# FRONT_CONN.net
KiCad netlist of a schematic drawn in Altium Designer
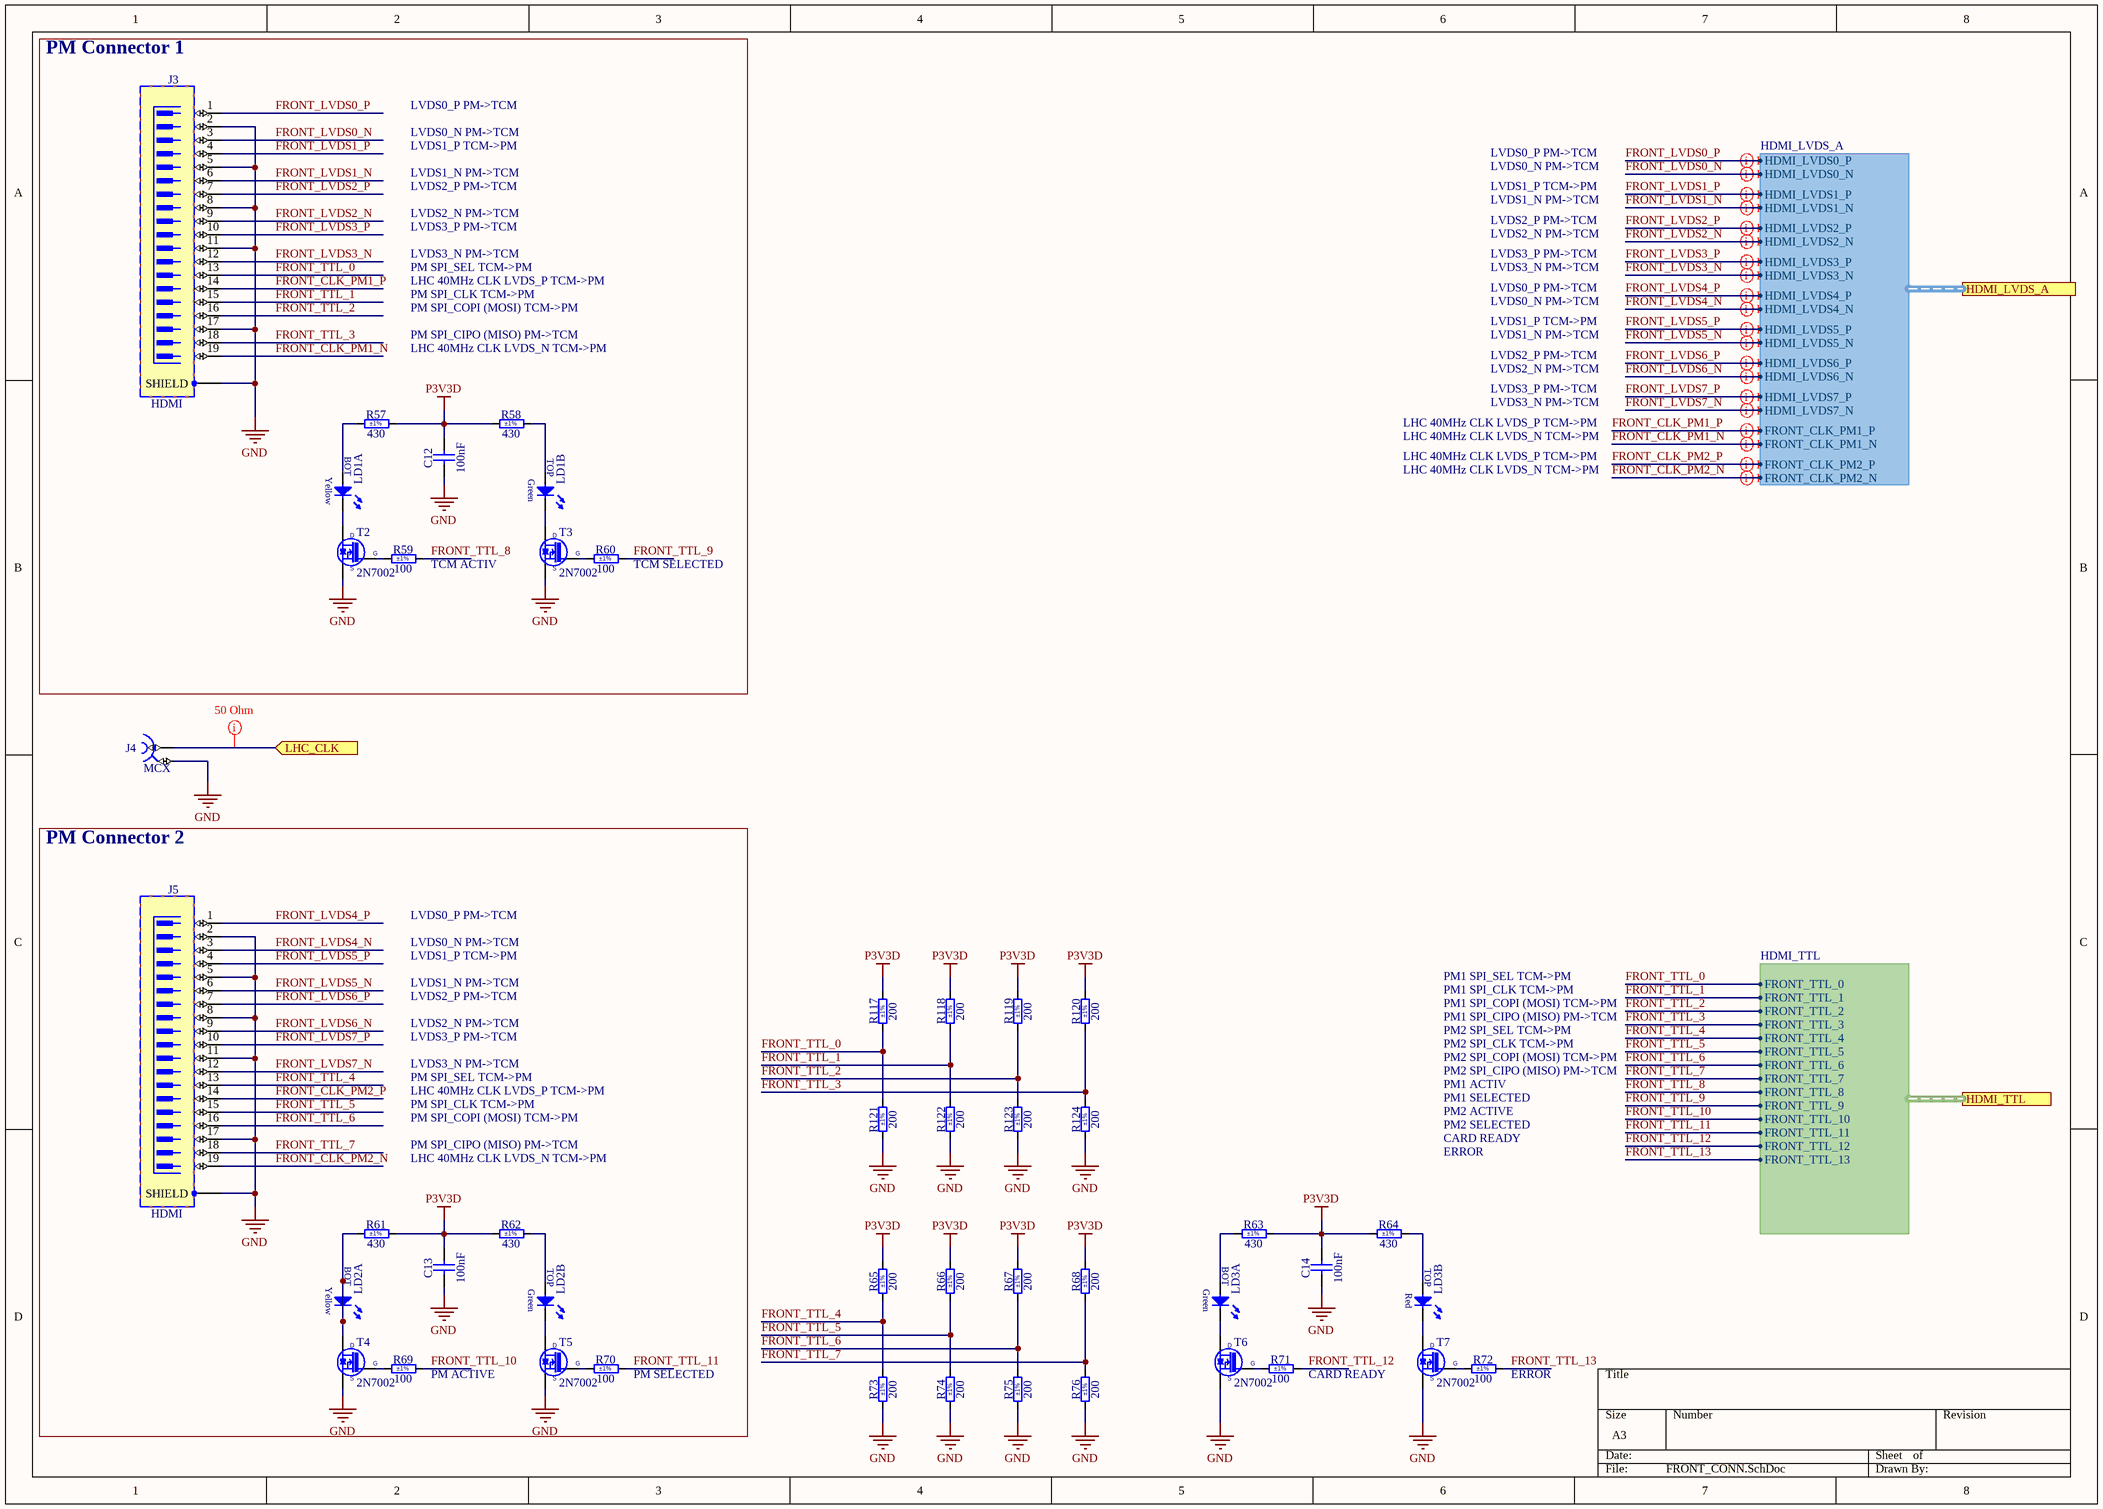
[diagram p0: FRONT_CONN.SchDoc]

(export (version "E")
  (design (tool "Eeschema 10.0.6"))
  (components
    (comp (ref "C12")
      (value "100nF")
      (footprint "CAPC1608X87N")
      (description "Non-polarised capacitor")
      (fields
        (field (name "PART NUMBER") "CC0603_100NF_50V_10%_X7R")
        (field (name "VOLTAGE") "50V")
        (field (name "AUTHOR") "CERN DEM JLC")
      )
      (libsource (lib "Capacitors") (part "Capacitor - non polarized"))
    )
    (comp (ref "C13")
      (value "100nF")
      (footprint "CAPC1608X87N")
      (description "Non-polarised capacitor")
      (fields
        (field (name "PART NUMBER") "CC0603_100NF_50V_10%_X7R")
        (field (name "VOLTAGE") "50V")
        (field (name "AUTHOR") "CERN DEM JLC")
      )
      (libsource (lib "Capacitors") (part "Capacitor - non polarized"))
    )
    (comp (ref "C14")
      (value "100nF")
      (footprint "CAPC1608X87N")
      (description "Non-polarised capacitor")
      (fields
        (field (name "PART NUMBER") "CC0603_100NF_50V_10%_X7R")
        (field (name "VOLTAGE") "50V")
        (field (name "AUTHOR") "CERN DEM JLC")
      )
      (libsource (lib "Capacitors") (part "Capacitor - non polarized"))
    )
    (comp (ref "J3")
      (value "HDMI")
      (footprint "TYCO_2007435-1")
      (description "Connector HDMI 19 Male + 1 Shield")
      (fields
        (field (name "PART NUMBER") "TYCO_2007435-1")
        (field (name "MANUFACTURER") "TYCO ELECTRONICS")
        (field (name "AUTHOR") "CERN DEM MR")
      )
      (libsource (lib "Connectors") (part "Connector HDMI 19 Male + 1 Shield"))
    )
    (comp (ref "J4")
      (value "MCX")
      (footprint "AMPHENOL_919-383J-51A")
      (fields
        (field (name "PART NUMBER") "AMPHENOL_919-383J-51A")
        (field (name "MANUFACTURER") "AMPHENOL")
        (field (name "MANUFACTURER PART NUMBER") "919-383J-51A")
        (field (name "AUTHOR") "CERN DEM BC")
      )
      (libsource (lib "Connectors") (part "Coax_1Female_1Shield"))
    )
    (comp (ref "J5")
      (value "HDMI")
      (footprint "TYCO_2007435-1")
      (description "Connector HDMI 19 Male + 1 Shield")
      (fields
        (field (name "PART NUMBER") "TYCO_2007435-1")
        (field (name "MANUFACTURER") "TYCO ELECTRONICS")
        (field (name "AUTHOR") "CERN DEM MR")
      )
      (libsource (lib "Connectors") (part "Connector HDMI 19 Male + 1 Shield"))
    )
    (comp (ref "LD1")
      (value "Green/Yellow")
      (footprint "LED_DIALIGHT_571-0123F")
      (description "2x LED  Botom Yellow, Top Green")
      (fields
        (field (name "PART NUMBER") "LED_DIALIGHT_571-0123F")
        (field (name "MANUFACTURER") "DIALIGHT")
        (field (name "AUTHOR") "CERN DEM JLC")
      )
      (libsource (lib "ICs And Semiconductors") (part "LED x2 Y-1C2A-BOT_G-3C4A-TOP"))
    )
    (comp (ref "LD2")
      (value "Green/Yellow")
      (footprint "LED_DIALIGHT_571-0123F")
      (description "2x LED  Botom Yellow, Top Green")
      (fields
        (field (name "PART NUMBER") "LED_DIALIGHT_571-0123F")
        (field (name "MANUFACTURER") "DIALIGHT")
        (field (name "AUTHOR") "CERN DEM JLC")
      )
      (libsource (lib "ICs And Semiconductors") (part "LED x2 Y-1C2A-BOT_G-3C4A-TOP"))
    )
    (comp (ref "LD3")
      (value "Red/Green")
      (footprint "LED_DIALIGHT_571-0112-100F")
      (description "2x LED Botom Green, Top Red")
      (fields
        (field (name "PART NUMBER") "LED_DIALIGHT_571-0112-100F")
        (field (name "MANUFACTURER") "DIALIGHT")
        (field (name "AUTHOR") "CERN DEM JLC")
      )
      (libsource (lib "ICs And Semiconductors") (part "LED x2 G-1C2A-BOT_R-3C4A-TOP"))
    )
    (comp (ref "R57")
      (value "430")
      (footprint "RESC1608X55N")
      (description "Resistor - 1%")
      (fields
        (field (name "TOLERANCE") "±1%")
        (field (name "PART NUMBER") "R0603_430R_1%_0.1W_100PPM")
        (field (name "POWER") "0.1W")
        (field (name "AUTHOR") "CERN DEM JLC")
      )
      (libsource (lib "Resistors") (part "Resistor - 1%"))
    )
    (comp (ref "R58")
      (value "430")
      (footprint "RESC1608X55N")
      (description "Resistor - 1%")
      (fields
        (field (name "TOLERANCE") "±1%")
        (field (name "PART NUMBER") "R0603_430R_1%_0.1W_100PPM")
        (field (name "POWER") "0.1W")
        (field (name "AUTHOR") "CERN DEM JLC")
      )
      (libsource (lib "Resistors") (part "Resistor - 1%"))
    )
    (comp (ref "R59")
      (value "100")
      (footprint "RESC1608X55N")
      (description "Resistor - 1%")
      (fields
        (field (name "TOLERANCE") "±1%")
        (field (name "PART NUMBER") "R0603_100R_1%_0.1W_100PPM")
        (field (name "POWER") "0.1W")
        (field (name "AUTHOR") "CERN DEM JLC")
      )
      (libsource (lib "Resistors") (part "Resistor - 1%"))
    )
    (comp (ref "R60")
      (value "100")
      (footprint "RESC1608X55N")
      (description "Resistor - 1%")
      (fields
        (field (name "TOLERANCE") "±1%")
        (field (name "PART NUMBER") "R0603_100R_1%_0.1W_100PPM")
        (field (name "POWER") "0.1W")
        (field (name "AUTHOR") "CERN DEM JLC")
      )
      (libsource (lib "Resistors") (part "Resistor - 1%"))
    )
    (comp (ref "R61")
      (value "430")
      (footprint "RESC1608X55N")
      (description "Resistor - 1%")
      (fields
        (field (name "TOLERANCE") "±1%")
        (field (name "PART NUMBER") "R0603_430R_1%_0.1W_100PPM")
        (field (name "POWER") "0.1W")
        (field (name "AUTHOR") "CERN DEM JLC")
      )
      (libsource (lib "Resistors") (part "Resistor - 1%"))
    )
    (comp (ref "R62")
      (value "430")
      (footprint "RESC1608X55N")
      (description "Resistor - 1%")
      (fields
        (field (name "TOLERANCE") "±1%")
        (field (name "PART NUMBER") "R0603_430R_1%_0.1W_100PPM")
        (field (name "POWER") "0.1W")
        (field (name "AUTHOR") "CERN DEM JLC")
      )
      (libsource (lib "Resistors") (part "Resistor - 1%"))
    )
    (comp (ref "R63")
      (value "430")
      (footprint "RESC1608X55N")
      (description "Resistor - 1%")
      (fields
        (field (name "TOLERANCE") "±1%")
        (field (name "PART NUMBER") "R0603_430R_1%_0.1W_100PPM")
        (field (name "POWER") "0.1W")
        (field (name "AUTHOR") "CERN DEM JLC")
      )
      (libsource (lib "Resistors") (part "Resistor - 1%"))
    )
    (comp (ref "R64")
      (value "430")
      (footprint "RESC1608X55N")
      (description "Resistor - 1%")
      (fields
        (field (name "TOLERANCE") "±1%")
        (field (name "PART NUMBER") "R0603_430R_1%_0.1W_100PPM")
        (field (name "POWER") "0.1W")
        (field (name "AUTHOR") "CERN DEM JLC")
      )
      (libsource (lib "Resistors") (part "Resistor - 1%"))
    )
    (comp (ref "R65")
      (value "200")
      (footprint "RESC1608X55N")
      (description "Resistor - 1%")
      (fields
        (field (name "TOLERANCE") "±1%")
        (field (name "PART NUMBER") "R0603_200R_1%_0.1W_100PPM")
        (field (name "POWER") "0.1W")
        (field (name "AUTHOR") "CERN DEM JLC")
      )
      (libsource (lib "Resistors") (part "Resistor - 1%"))
    )
    (comp (ref "R66")
      (value "200")
      (footprint "RESC1608X55N")
      (description "Resistor - 1%")
      (fields
        (field (name "TOLERANCE") "±1%")
        (field (name "PART NUMBER") "R0603_200R_1%_0.1W_100PPM")
        (field (name "POWER") "0.1W")
        (field (name "AUTHOR") "CERN DEM JLC")
      )
      (libsource (lib "Resistors") (part "Resistor - 1%"))
    )
    (comp (ref "R67")
      (value "200")
      (footprint "RESC1608X55N")
      (description "Resistor - 1%")
      (fields
        (field (name "TOLERANCE") "±1%")
        (field (name "PART NUMBER") "R0603_200R_1%_0.1W_100PPM")
        (field (name "POWER") "0.1W")
        (field (name "AUTHOR") "CERN DEM JLC")
      )
      (libsource (lib "Resistors") (part "Resistor - 1%"))
    )
    (comp (ref "R68")
      (value "200")
      (footprint "RESC1608X55N")
      (description "Resistor - 1%")
      (fields
        (field (name "TOLERANCE") "±1%")
        (field (name "PART NUMBER") "R0603_200R_1%_0.1W_100PPM")
        (field (name "POWER") "0.1W")
        (field (name "AUTHOR") "CERN DEM JLC")
      )
      (libsource (lib "Resistors") (part "Resistor - 1%"))
    )
    (comp (ref "R69")
      (value "100")
      (footprint "RESC1608X55N")
      (description "Resistor - 1%")
      (fields
        (field (name "TOLERANCE") "±1%")
        (field (name "PART NUMBER") "R0603_100R_1%_0.1W_100PPM")
        (field (name "POWER") "0.1W")
        (field (name "AUTHOR") "CERN DEM JLC")
      )
      (libsource (lib "Resistors") (part "Resistor - 1%"))
    )
    (comp (ref "R70")
      (value "100")
      (footprint "RESC1608X55N")
      (description "Resistor - 1%")
      (fields
        (field (name "TOLERANCE") "±1%")
        (field (name "PART NUMBER") "R0603_100R_1%_0.1W_100PPM")
        (field (name "POWER") "0.1W")
        (field (name "AUTHOR") "CERN DEM JLC")
      )
      (libsource (lib "Resistors") (part "Resistor - 1%"))
    )
    (comp (ref "R71")
      (value "100")
      (footprint "RESC1608X55N")
      (description "Resistor - 1%")
      (fields
        (field (name "TOLERANCE") "±1%")
        (field (name "PART NUMBER") "R0603_100R_1%_0.1W_100PPM")
        (field (name "POWER") "0.1W")
        (field (name "AUTHOR") "CERN DEM JLC")
      )
      (libsource (lib "Resistors") (part "Resistor - 1%"))
    )
    (comp (ref "R72")
      (value "100")
      (footprint "RESC1608X55N")
      (description "Resistor - 1%")
      (fields
        (field (name "TOLERANCE") "±1%")
        (field (name "PART NUMBER") "R0603_100R_1%_0.1W_100PPM")
        (field (name "POWER") "0.1W")
        (field (name "AUTHOR") "CERN DEM JLC")
      )
      (libsource (lib "Resistors") (part "Resistor - 1%"))
    )
    (comp (ref "R73")
      (value "200")
      (footprint "RESC1608X55N")
      (description "Resistor - 1%")
      (fields
        (field (name "TOLERANCE") "±1%")
        (field (name "PART NUMBER") "R0603_200R_1%_0.1W_100PPM")
        (field (name "POWER") "0.1W")
        (field (name "AUTHOR") "CERN DEM JLC")
      )
      (libsource (lib "Resistors") (part "Resistor - 1%"))
    )
    (comp (ref "R74")
      (value "200")
      (footprint "RESC1608X55N")
      (description "Resistor - 1%")
      (fields
        (field (name "TOLERANCE") "±1%")
        (field (name "PART NUMBER") "R0603_200R_1%_0.1W_100PPM")
        (field (name "POWER") "0.1W")
        (field (name "AUTHOR") "CERN DEM JLC")
      )
      (libsource (lib "Resistors") (part "Resistor - 1%"))
    )
    (comp (ref "R75")
      (value "200")
      (footprint "RESC1608X55N")
      (description "Resistor - 1%")
      (fields
        (field (name "TOLERANCE") "±1%")
        (field (name "PART NUMBER") "R0603_200R_1%_0.1W_100PPM")
        (field (name "POWER") "0.1W")
        (field (name "AUTHOR") "CERN DEM JLC")
      )
      (libsource (lib "Resistors") (part "Resistor - 1%"))
    )
    (comp (ref "R76")
      (value "200")
      (footprint "RESC1608X55N")
      (description "Resistor - 1%")
      (fields
        (field (name "TOLERANCE") "±1%")
        (field (name "PART NUMBER") "R0603_200R_1%_0.1W_100PPM")
        (field (name "POWER") "0.1W")
        (field (name "AUTHOR") "CERN DEM JLC")
      )
      (libsource (lib "Resistors") (part "Resistor - 1%"))
    )
    (comp (ref "R117")
      (value "200")
      (footprint "RESC1608X55N")
      (description "Resistor - 1%")
      (fields
        (field (name "TOLERANCE") "±1%")
        (field (name "PART NUMBER") "R0603_200R_1%_0.1W_100PPM")
        (field (name "POWER") "0.1W")
        (field (name "AUTHOR") "CERN DEM JLC")
      )
      (libsource (lib "Resistors") (part "Resistor - 1%"))
    )
    (comp (ref "R118")
      (value "200")
      (footprint "RESC1608X55N")
      (description "Resistor - 1%")
      (fields
        (field (name "TOLERANCE") "±1%")
        (field (name "PART NUMBER") "R0603_200R_1%_0.1W_100PPM")
        (field (name "POWER") "0.1W")
        (field (name "AUTHOR") "CERN DEM JLC")
      )
      (libsource (lib "Resistors") (part "Resistor - 1%"))
    )
    (comp (ref "R119")
      (value "200")
      (footprint "RESC1608X55N")
      (description "Resistor - 1%")
      (fields
        (field (name "TOLERANCE") "±1%")
        (field (name "PART NUMBER") "R0603_200R_1%_0.1W_100PPM")
        (field (name "POWER") "0.1W")
        (field (name "AUTHOR") "CERN DEM JLC")
      )
      (libsource (lib "Resistors") (part "Resistor - 1%"))
    )
    (comp (ref "R120")
      (value "200")
      (footprint "RESC1608X55N")
      (description "Resistor - 1%")
      (fields
        (field (name "TOLERANCE") "±1%")
        (field (name "PART NUMBER") "R0603_200R_1%_0.1W_100PPM")
        (field (name "POWER") "0.1W")
        (field (name "AUTHOR") "CERN DEM JLC")
      )
      (libsource (lib "Resistors") (part "Resistor - 1%"))
    )
    (comp (ref "R121")
      (value "200")
      (footprint "RESC1608X55N")
      (description "Resistor - 1%")
      (fields
        (field (name "TOLERANCE") "±1%")
        (field (name "PART NUMBER") "R0603_200R_1%_0.1W_100PPM")
        (field (name "POWER") "0.1W")
        (field (name "AUTHOR") "CERN DEM JLC")
      )
      (libsource (lib "Resistors") (part "Resistor - 1%"))
    )
    (comp (ref "R122")
      (value "200")
      (footprint "RESC1608X55N")
      (description "Resistor - 1%")
      (fields
        (field (name "TOLERANCE") "±1%")
        (field (name "PART NUMBER") "R0603_200R_1%_0.1W_100PPM")
        (field (name "POWER") "0.1W")
        (field (name "AUTHOR") "CERN DEM JLC")
      )
      (libsource (lib "Resistors") (part "Resistor - 1%"))
    )
    (comp (ref "R123")
      (value "200")
      (footprint "RESC1608X55N")
      (description "Resistor - 1%")
      (fields
        (field (name "TOLERANCE") "±1%")
        (field (name "PART NUMBER") "R0603_200R_1%_0.1W_100PPM")
        (field (name "POWER") "0.1W")
        (field (name "AUTHOR") "CERN DEM JLC")
      )
      (libsource (lib "Resistors") (part "Resistor - 1%"))
    )
    (comp (ref "R124")
      (value "200")
      (footprint "RESC1608X55N")
      (description "Resistor - 1%")
      (fields
        (field (name "TOLERANCE") "±1%")
        (field (name "PART NUMBER") "R0603_200R_1%_0.1W_100PPM")
        (field (name "POWER") "0.1W")
        (field (name "AUTHOR") "CERN DEM JLC")
      )
      (libsource (lib "Resistors") (part "Resistor - 1%"))
    )
    (comp (ref "T2")
      (value "2N7002")
      (footprint "SOT95P240X130-3N")
      (description "N-CHANNEL MOSFET WITH DIODE")
      (fields (field (name "MANUFACTURER") "FAIRCHILD SEMICONDUCTOR") (field (name "AUTHOR") "CERN DEM JLC"))
      (libsource (lib "ICs And Semiconductors") (part "N-MOSFET-D 1G 2S 3D"))
    )
    (comp (ref "T3")
      (value "2N7002")
      (footprint "SOT95P240X130-3N")
      (description "N-CHANNEL MOSFET WITH DIODE")
      (fields (field (name "MANUFACTURER") "FAIRCHILD SEMICONDUCTOR") (field (name "AUTHOR") "CERN DEM JLC"))
      (libsource (lib "ICs And Semiconductors") (part "N-MOSFET-D 1G 2S 3D"))
    )
    (comp (ref "T4")
      (value "2N7002")
      (footprint "SOT95P240X130-3N")
      (description "N-CHANNEL MOSFET WITH DIODE")
      (fields (field (name "MANUFACTURER") "FAIRCHILD SEMICONDUCTOR") (field (name "AUTHOR") "CERN DEM JLC"))
      (libsource (lib "ICs And Semiconductors") (part "N-MOSFET-D 1G 2S 3D"))
    )
    (comp (ref "T5")
      (value "2N7002")
      (footprint "SOT95P240X130-3N")
      (description "N-CHANNEL MOSFET WITH DIODE")
      (fields (field (name "MANUFACTURER") "FAIRCHILD SEMICONDUCTOR") (field (name "AUTHOR") "CERN DEM JLC"))
      (libsource (lib "ICs And Semiconductors") (part "N-MOSFET-D 1G 2S 3D"))
    )
    (comp (ref "T6")
      (value "2N7002")
      (footprint "SOT95P240X130-3N")
      (description "N-CHANNEL MOSFET WITH DIODE")
      (fields (field (name "MANUFACTURER") "FAIRCHILD SEMICONDUCTOR") (field (name "AUTHOR") "CERN DEM JLC"))
      (libsource (lib "ICs And Semiconductors") (part "N-MOSFET-D 1G 2S 3D"))
    )
    (comp (ref "T7")
      (value "2N7002")
      (footprint "SOT95P240X130-3N")
      (description "N-CHANNEL MOSFET WITH DIODE")
      (fields (field (name "MANUFACTURER") "FAIRCHILD SEMICONDUCTOR") (field (name "AUTHOR") "CERN DEM JLC"))
      (libsource (lib "ICs And Semiconductors") (part "N-MOSFET-D 1G 2S 3D"))
    )
  )
  (nets
    (net (code "3") (name "/FRONT_CLK_PM1_N") (class "Default")
      (node (ref "J3") (pin "19") (pinfunction "19_19") (pintype "bidirectional"))
    )
    (net (code "4") (name "/FRONT_CLK_PM1_P") (class "Default")
      (node (ref "J3") (pin "14") (pinfunction "14_14") (pintype "bidirectional"))
    )
    (net (code "5") (name "/FRONT_CLK_PM2_N") (class "Default")
      (node (ref "J5") (pin "19") (pinfunction "19_19") (pintype "bidirectional"))
    )
    (net (code "6") (name "/FRONT_CLK_PM2_P") (class "Default")
      (node (ref "J5") (pin "14") (pinfunction "14_14") (pintype "bidirectional"))
    )
    (net (code "7") (name "/FRONT_LVDS0_N") (class "Default")
      (node (ref "J3") (pin "3") (pinfunction "3_3") (pintype "bidirectional"))
    )
    (net (code "8") (name "/FRONT_LVDS0_P") (class "Default")
      (node (ref "J3") (pin "1") (pinfunction "1_1") (pintype "bidirectional"))
    )
    (net (code "9") (name "/FRONT_LVDS1_N") (class "Default")
      (node (ref "J3") (pin "6") (pinfunction "6_6") (pintype "bidirectional"))
    )
    (net (code "10") (name "/FRONT_LVDS1_P") (class "Default")
      (node (ref "J3") (pin "4") (pinfunction "4_4") (pintype "bidirectional"))
    )
    (net (code "11") (name "/FRONT_LVDS2_N") (class "Default")
      (node (ref "J3") (pin "9") (pinfunction "9_9") (pintype "bidirectional"))
    )
    (net (code "12") (name "/FRONT_LVDS2_P") (class "Default")
      (node (ref "J3") (pin "7") (pinfunction "7_7") (pintype "bidirectional"))
    )
    (net (code "13") (name "/FRONT_LVDS3_N") (class "Default")
      (node (ref "J3") (pin "12") (pinfunction "12_12") (pintype "bidirectional"))
    )
    (net (code "14") (name "/FRONT_LVDS3_P") (class "Default")
      (node (ref "J3") (pin "10") (pinfunction "10_10") (pintype "bidirectional"))
    )
    (net (code "15") (name "/FRONT_LVDS4_N") (class "Default")
      (node (ref "J5") (pin "3") (pinfunction "3_3") (pintype "bidirectional"))
    )
    (net (code "16") (name "/FRONT_LVDS4_P") (class "Default")
      (node (ref "J5") (pin "1") (pinfunction "1_1") (pintype "bidirectional"))
    )
    (net (code "17") (name "/FRONT_LVDS5_N") (class "Default")
      (node (ref "J5") (pin "6") (pinfunction "6_6") (pintype "bidirectional"))
    )
    (net (code "18") (name "/FRONT_LVDS5_P") (class "Default")
      (node (ref "J5") (pin "4") (pinfunction "4_4") (pintype "bidirectional"))
    )
    (net (code "19") (name "/FRONT_LVDS6_N") (class "Default")
      (node (ref "J5") (pin "9") (pinfunction "9_9") (pintype "bidirectional"))
    )
    (net (code "20") (name "/FRONT_LVDS6_P") (class "Default")
      (node (ref "J5") (pin "7") (pinfunction "7_7") (pintype "bidirectional"))
    )
    (net (code "21") (name "/FRONT_LVDS7_N") (class "Default")
      (node (ref "J5") (pin "12") (pinfunction "12_12") (pintype "bidirectional"))
    )
    (net (code "22") (name "/FRONT_LVDS7_P") (class "Default")
      (node (ref "J5") (pin "10") (pinfunction "10_10") (pintype "bidirectional"))
    )
    (net (code "23") (name "/FRONT_TTL_0") (class "Default")
      (node (ref "J3") (pin "13") (pinfunction "13_13") (pintype "bidirectional"))
      (node (ref "R117") (pin "1") (pinfunction "1_1") (pintype "passive"))
      (node (ref "R121") (pin "2") (pinfunction "2_2") (pintype "passive"))
    )
    (net (code "24") (name "/FRONT_TTL_1") (class "Default")
      (node (ref "J3") (pin "15") (pinfunction "15_15") (pintype "bidirectional"))
      (node (ref "R118") (pin "1") (pinfunction "1_1") (pintype "passive"))
      (node (ref "R122") (pin "2") (pinfunction "2_2") (pintype "passive"))
    )
    (net (code "25") (name "/FRONT_TTL_2") (class "Default")
      (node (ref "J3") (pin "16") (pinfunction "16_16") (pintype "bidirectional"))
      (node (ref "R119") (pin "1") (pinfunction "1_1") (pintype "passive"))
      (node (ref "R123") (pin "2") (pinfunction "2_2") (pintype "passive"))
    )
    (net (code "26") (name "/FRONT_TTL_3") (class "Default")
      (node (ref "J3") (pin "18") (pinfunction "18_18") (pintype "bidirectional"))
      (node (ref "R120") (pin "1") (pinfunction "1_1") (pintype "passive"))
      (node (ref "R124") (pin "2") (pinfunction "2_2") (pintype "passive"))
    )
    (net (code "27") (name "/FRONT_TTL_4") (class "Default")
      (node (ref "J5") (pin "13") (pinfunction "13_13") (pintype "bidirectional"))
      (node (ref "R65") (pin "1") (pinfunction "1_1") (pintype "passive"))
      (node (ref "R73") (pin "2") (pinfunction "2_2") (pintype "passive"))
    )
    (net (code "28") (name "/FRONT_TTL_5") (class "Default")
      (node (ref "J5") (pin "15") (pinfunction "15_15") (pintype "bidirectional"))
      (node (ref "R66") (pin "1") (pinfunction "1_1") (pintype "passive"))
      (node (ref "R74") (pin "2") (pinfunction "2_2") (pintype "passive"))
    )
    (net (code "29") (name "/FRONT_TTL_6") (class "Default")
      (node (ref "J5") (pin "16") (pinfunction "16_16") (pintype "bidirectional"))
      (node (ref "R67") (pin "1") (pinfunction "1_1") (pintype "passive"))
      (node (ref "R75") (pin "2") (pinfunction "2_2") (pintype "passive"))
    )
    (net (code "30") (name "/FRONT_TTL_7") (class "Default")
      (node (ref "J5") (pin "18") (pinfunction "18_18") (pintype "bidirectional"))
      (node (ref "R68") (pin "1") (pinfunction "1_1") (pintype "passive"))
      (node (ref "R76") (pin "2") (pinfunction "2_2") (pintype "passive"))
    )
    (net (code "31") (name "/FRONT_TTL_8") (class "Default")
      (node (ref "R59") (pin "2") (pinfunction "2_2") (pintype "passive"))
    )
    (net (code "32") (name "/FRONT_TTL_9") (class "Default")
      (node (ref "R60") (pin "2") (pinfunction "2_2") (pintype "passive"))
    )
    (net (code "33") (name "/FRONT_TTL_10") (class "Default")
      (node (ref "R69") (pin "2") (pinfunction "2_2") (pintype "passive"))
    )
    (net (code "34") (name "/FRONT_TTL_11") (class "Default")
      (node (ref "R70") (pin "2") (pinfunction "2_2") (pintype "passive"))
    )
    (net (code "35") (name "/FRONT_TTL_12") (class "Default")
      (node (ref "R71") (pin "2") (pinfunction "2_2") (pintype "passive"))
    )
    (net (code "36") (name "/FRONT_TTL_13") (class "Default")
      (node (ref "R72") (pin "2") (pinfunction "2_2") (pintype "passive"))
    )
    (net (code "37") (name "/LHC_CLK") (class "Default")
      (node (ref "J4") (pin "1") (pinfunction "1_1") (pintype "bidirectional"))
    )
    (net (code "40") (name "GND") (class "Default")
      (node (ref "C12") (pin "1") (pinfunction "1_1") (pintype "passive"))
      (node (ref "C13") (pin "1") (pinfunction "1_1") (pintype "passive"))
      (node (ref "C14") (pin "1") (pinfunction "1_1") (pintype "passive"))
      (node (ref "J3") (pin "11") (pinfunction "11_11") (pintype "bidirectional"))
      (node (ref "J3") (pin "17") (pinfunction "17_17") (pintype "bidirectional"))
      (node (ref "J3") (pin "2") (pinfunction "2_2") (pintype "bidirectional"))
      (node (ref "J3") (pin "5") (pinfunction "5_5") (pintype "bidirectional"))
      (node (ref "J3") (pin "8") (pinfunction "8_8") (pintype "bidirectional"))
      (node (ref "J3") (pin "SHIELD") (pinfunction "SHIELD_SHIELD") (pintype "power_in"))
      (node (ref "J4") (pin "2") (pinfunction "2_2") (pintype "bidirectional"))
      (node (ref "J5") (pin "11") (pinfunction "11_11") (pintype "bidirectional"))
      (node (ref "J5") (pin "17") (pinfunction "17_17") (pintype "bidirectional"))
      (node (ref "J5") (pin "2") (pinfunction "2_2") (pintype "bidirectional"))
      (node (ref "J5") (pin "5") (pinfunction "5_5") (pintype "bidirectional"))
      (node (ref "J5") (pin "8") (pinfunction "8_8") (pintype "bidirectional"))
      (node (ref "J5") (pin "SHIELD") (pinfunction "SHIELD_SHIELD") (pintype "power_in"))
      (node (ref "R121") (pin "1") (pinfunction "1_1") (pintype "passive"))
      (node (ref "R122") (pin "1") (pinfunction "1_1") (pintype "passive"))
      (node (ref "R123") (pin "1") (pinfunction "1_1") (pintype "passive"))
      (node (ref "R124") (pin "1") (pinfunction "1_1") (pintype "passive"))
      (node (ref "R73") (pin "1") (pinfunction "1_1") (pintype "passive"))
      (node (ref "R74") (pin "1") (pinfunction "1_1") (pintype "passive"))
      (node (ref "R75") (pin "1") (pinfunction "1_1") (pintype "passive"))
      (node (ref "R76") (pin "1") (pinfunction "1_1") (pintype "passive"))
      (node (ref "T2") (pin "2") (pinfunction "S_2") (pintype "passive"))
      (node (ref "T3") (pin "2") (pinfunction "S_2") (pintype "passive"))
      (node (ref "T4") (pin "2") (pinfunction "S_2") (pintype "passive"))
      (node (ref "T5") (pin "2") (pinfunction "S_2") (pintype "passive"))
      (node (ref "T6") (pin "2") (pinfunction "S_2") (pintype "passive"))
      (node (ref "T7") (pin "2") (pinfunction "S_2") (pintype "passive"))
    )
    (net (code "41") (name "Net-(LD1A-A)") (class "Default")
      (node (ref "LD1") (pin "2") (pinfunction "A_2") (pintype "passive"))
      (node (ref "R57") (pin "1") (pinfunction "1_1") (pintype "passive"))
    )
    (net (code "42") (name "Net-(LD1A-C)") (class "Default")
      (node (ref "LD1") (pin "1") (pinfunction "C_1") (pintype "passive"))
      (node (ref "T2") (pin "3") (pinfunction "D_3") (pintype "passive"))
    )
    (net (code "43") (name "Net-(LD1B-A)") (class "Default")
      (node (ref "LD1") (pin "4") (pinfunction "A_4") (pintype "passive"))
      (node (ref "R58") (pin "2") (pinfunction "2_2") (pintype "passive"))
    )
    (net (code "44") (name "Net-(LD1B-C)") (class "Default")
      (node (ref "LD1") (pin "3") (pinfunction "C_3") (pintype "passive"))
      (node (ref "T3") (pin "3") (pinfunction "D_3") (pintype "passive"))
    )
    (net (code "45") (name "Net-(LD2A-A)") (class "Default")
      (node (ref "LD2") (pin "1") (pinfunction "C_1") (pintype "passive"))
      (node (ref "LD2") (pin "2") (pinfunction "A_2") (pintype "passive"))
      (node (ref "R61") (pin "1") (pinfunction "1_1") (pintype "passive"))
      (node (ref "T4") (pin "3") (pinfunction "D_3") (pintype "passive"))
    )
    (net (code "46") (name "Net-(LD2B-A)") (class "Default")
      (node (ref "LD2") (pin "4") (pinfunction "A_4") (pintype "passive"))
      (node (ref "R62") (pin "2") (pinfunction "2_2") (pintype "passive"))
    )
    (net (code "47") (name "Net-(LD2B-C)") (class "Default")
      (node (ref "LD2") (pin "3") (pinfunction "C_3") (pintype "passive"))
      (node (ref "T5") (pin "3") (pinfunction "D_3") (pintype "passive"))
    )
    (net (code "48") (name "Net-(LD3A-A)") (class "Default")
      (node (ref "LD3") (pin "2") (pinfunction "A_2") (pintype "passive"))
      (node (ref "R63") (pin "1") (pinfunction "1_1") (pintype "passive"))
    )
    (net (code "49") (name "Net-(LD3A-C)") (class "Default")
      (node (ref "LD3") (pin "1") (pinfunction "C_1") (pintype "passive"))
      (node (ref "T6") (pin "3") (pinfunction "D_3") (pintype "passive"))
    )
    (net (code "50") (name "Net-(LD3B-A)") (class "Default")
      (node (ref "LD3") (pin "4") (pinfunction "A_4") (pintype "passive"))
      (node (ref "R64") (pin "2") (pinfunction "2_2") (pintype "passive"))
    )
    (net (code "51") (name "Net-(LD3B-C)") (class "Default")
      (node (ref "LD3") (pin "3") (pinfunction "C_3") (pintype "passive"))
      (node (ref "T7") (pin "3") (pinfunction "D_3") (pintype "passive"))
    )
    (net (code "52") (name "Net-(T2-G)") (class "Default")
      (node (ref "R59") (pin "1") (pinfunction "1_1") (pintype "passive"))
      (node (ref "T2") (pin "1") (pinfunction "G_1") (pintype "passive"))
    )
    (net (code "53") (name "Net-(T3-G)") (class "Default")
      (node (ref "R60") (pin "1") (pinfunction "1_1") (pintype "passive"))
      (node (ref "T3") (pin "1") (pinfunction "G_1") (pintype "passive"))
    )
    (net (code "54") (name "Net-(T4-G)") (class "Default")
      (node (ref "R69") (pin "1") (pinfunction "1_1") (pintype "passive"))
      (node (ref "T4") (pin "1") (pinfunction "G_1") (pintype "passive"))
    )
    (net (code "55") (name "Net-(T5-G)") (class "Default")
      (node (ref "R70") (pin "1") (pinfunction "1_1") (pintype "passive"))
      (node (ref "T5") (pin "1") (pinfunction "G_1") (pintype "passive"))
    )
    (net (code "56") (name "Net-(T6-G)") (class "Default")
      (node (ref "R71") (pin "1") (pinfunction "1_1") (pintype "passive"))
      (node (ref "T6") (pin "1") (pinfunction "G_1") (pintype "passive"))
    )
    (net (code "57") (name "Net-(T7-G)") (class "Default")
      (node (ref "R72") (pin "1") (pinfunction "1_1") (pintype "passive"))
      (node (ref "T7") (pin "1") (pinfunction "G_1") (pintype "passive"))
    )
    (net (code "58") (name "P3V3D") (class "Default")
      (node (ref "C12") (pin "2") (pinfunction "2_2") (pintype "passive"))
      (node (ref "C13") (pin "2") (pinfunction "2_2") (pintype "passive"))
      (node (ref "C14") (pin "2") (pinfunction "2_2") (pintype "passive"))
      (node (ref "R117") (pin "2") (pinfunction "2_2") (pintype "passive"))
      (node (ref "R118") (pin "2") (pinfunction "2_2") (pintype "passive"))
      (node (ref "R119") (pin "2") (pinfunction "2_2") (pintype "passive"))
      (node (ref "R120") (pin "2") (pinfunction "2_2") (pintype "passive"))
      (node (ref "R57") (pin "2") (pinfunction "2_2") (pintype "passive"))
      (node (ref "R58") (pin "1") (pinfunction "1_1") (pintype "passive"))
      (node (ref "R61") (pin "2") (pinfunction "2_2") (pintype "passive"))
      (node (ref "R62") (pin "1") (pinfunction "1_1") (pintype "passive"))
      (node (ref "R63") (pin "2") (pinfunction "2_2") (pintype "passive"))
      (node (ref "R64") (pin "1") (pinfunction "1_1") (pintype "passive"))
      (node (ref "R65") (pin "2") (pinfunction "2_2") (pintype "passive"))
      (node (ref "R66") (pin "2") (pinfunction "2_2") (pintype "passive"))
      (node (ref "R67") (pin "2") (pinfunction "2_2") (pintype "passive"))
      (node (ref "R68") (pin "2") (pinfunction "2_2") (pintype "passive"))
    )
  )
)
